# Chessbot_v7.net
KiCad netlist of a schematic drawn in EAGLE
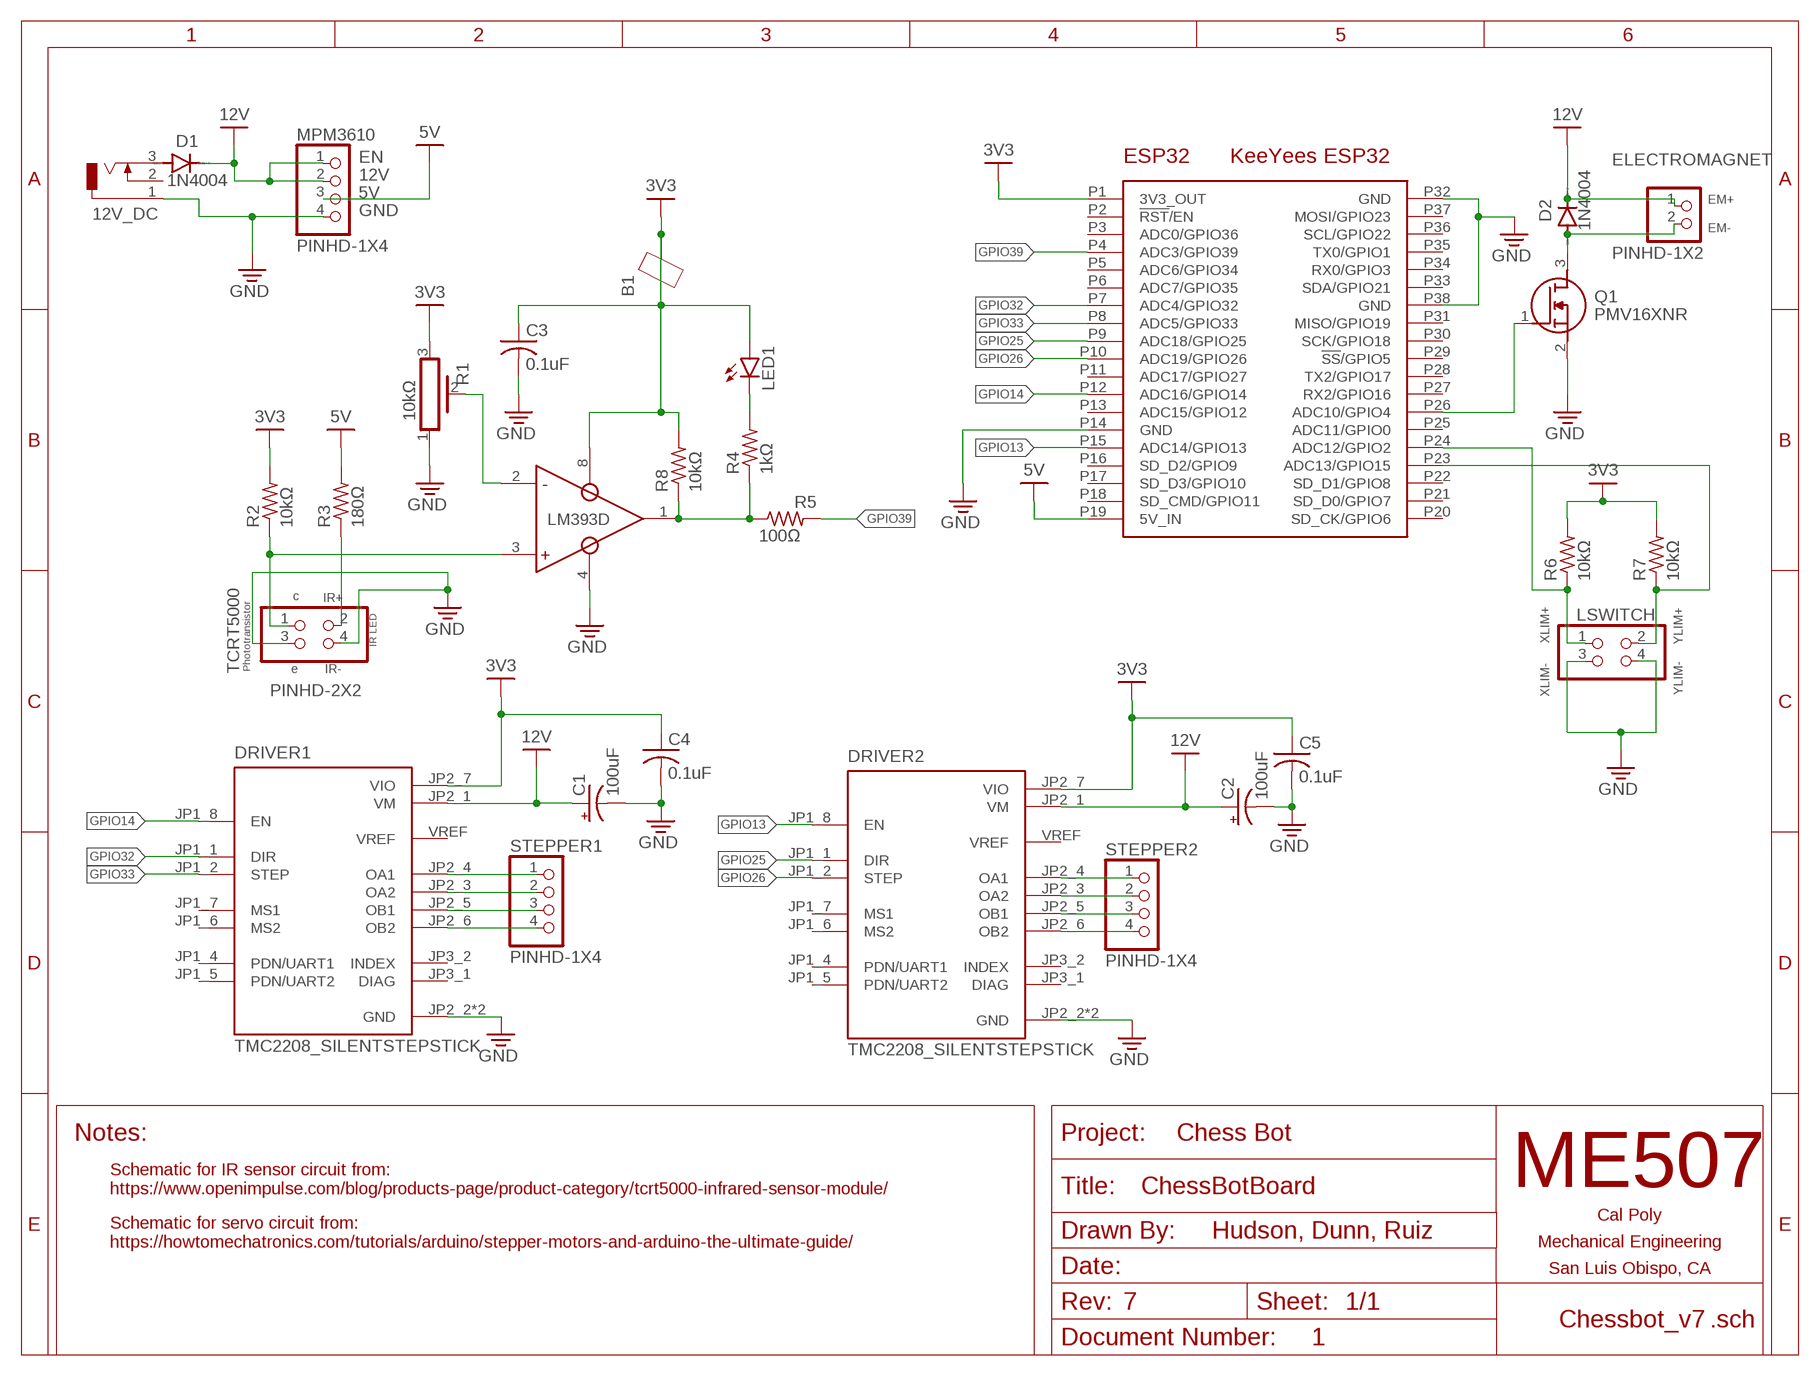
[diagram p0: schematic, sheet 1]

(export (version "E")
  (design (tool "Eeschema 10.0.6"))
  (components
    (comp (ref "12V_DC")
      (value "DCJ0303")
      (footprint "eagle-import:DCJ0303")
      (libsource (lib "eagle-import") (part "DCJ0303"))
    )
    (comp (ref "B1")
      (value "BEAD0805")
      (footprint "eagle-import:0805")
      (libsource (lib "eagle-import") (part "BEAD0805"))
    )
    (comp (ref "C1")
      (value "100uF")
      (footprint "eagle-import:E2,5-6")
      (libsource (lib "eagle-import") (part "CPOL-USE2.5-6"))
    )
    (comp (ref "C2")
      (value "100uF")
      (footprint "eagle-import:E2,5-6")
      (libsource (lib "eagle-import") (part "CPOL-USE2.5-6"))
    )
    (comp (ref "C3")
      (value "0.1uF")
      (footprint "eagle-import:C0805")
      (libsource (lib "eagle-import") (part "C-USC0805"))
    )
    (comp (ref "C4")
      (value "0.1uF")
      (footprint "eagle-import:C0805")
      (libsource (lib "eagle-import") (part "C-USC0805"))
    )
    (comp (ref "C5")
      (value "0.1uF")
      (footprint "eagle-import:C0805")
      (libsource (lib "eagle-import") (part "C-USC0805"))
    )
    (comp (ref "D1")
      (value "1N4004")
      (footprint "eagle-import:DO41-10")
      (libsource (lib "eagle-import") (part "1N4004"))
    )
    (comp (ref "D2")
      (value "1N4004")
      (footprint "eagle-import:DO41-10")
      (libsource (lib "eagle-import") (part "1N4004"))
    )
    (comp (ref "DRIVER1")
      (value "TMC2208_SILENTSTEPSTICK")
      (footprint "eagle-import:MODULE_TMC2208_SILENTSTEPSTICK")
      (fields (field (name "MF") "Trinamic Motion") (field (name "MP") "TMC2208 SILENTSTEPSTICK"))
      (libsource (lib "eagle-import") (part "TMC2208_SILENTSTEPSTICK"))
    )
    (comp (ref "DRIVER2")
      (value "TMC2208_SILENTSTEPSTICK")
      (footprint "eagle-import:MODULE_TMC2208_SILENTSTEPSTICK")
      (fields (field (name "MF") "Trinamic Motion") (field (name "MP") "TMC2208 SILENTSTEPSTICK"))
      (libsource (lib "eagle-import") (part "TMC2208_SILENTSTEPSTICK"))
    )
    (comp (ref "ELECTROMAGNET")
      (value "PINHD-1X2")
      (footprint "eagle-import:1X02")
      (libsource (lib "eagle-import") (part "PINHD-1X2"))
    )
    (comp (ref "ESP32")
      (value "KEEYEES_ESP32")
      (footprint "eagle-import:KEEYEES_ESP32")
      (libsource (lib "eagle-import") (part "KEEYEES_ESP32"))
    )
    (comp (ref "LED1")
      (value "LEDSMT1206")
      (footprint "eagle-import:1206")
      (libsource (lib "eagle-import") (part "LEDSMT1206"))
    )
    (comp (ref "LSWITCH")
      (value "PINHD-2X2")
      (footprint "eagle-import:2X02")
      (libsource (lib "eagle-import") (part "pinhead_325_PINHD-2X2"))
    )
    (comp (ref "MPM3610")
      (value "PINHD-1X4")
      (footprint "eagle-import:1X04")
      (libsource (lib "eagle-import") (part "PINHD-1X4"))
    )
    (comp (ref "Q1")
      (value "PMV16XNR")
      (footprint "eagle-import:SOT95P230X110-3N")
      (fields (field (name "MOUSER_PART_NUMBER") "771-PMV16XNR"))
      (libsource (lib "eagle-import") (part "PMV16XNR"))
    )
    (comp (ref "R1")
      (value "10kΩ")
      (footprint "eagle-import:PV36Z")
      (fields (field (name "MANUFACTURER") "BOURNS") (field (name "MPN") "PV36Z"))
      (libsource (lib "eagle-import") (part "PV36Z"))
    )
    (comp (ref "R2")
      (value "10kΩ")
      (footprint "eagle-import:R0805")
      (libsource (lib "eagle-import") (part "R-US_R0805"))
    )
    (comp (ref "R3")
      (value "180Ω")
      (footprint "eagle-import:R0805")
      (libsource (lib "eagle-import") (part "R-US_R0805"))
    )
    (comp (ref "R4")
      (value "1kΩ")
      (footprint "eagle-import:R0805")
      (libsource (lib "eagle-import") (part "R-US_R0805"))
    )
    (comp (ref "R5")
      (value "100Ω")
      (footprint "eagle-import:R0805")
      (libsource (lib "eagle-import") (part "R-US_R0805"))
    )
    (comp (ref "R6")
      (value "10kΩ")
      (footprint "eagle-import:R0805")
      (libsource (lib "eagle-import") (part "R-US_R0805"))
    )
    (comp (ref "R7")
      (value "10kΩ")
      (footprint "eagle-import:R0805")
      (libsource (lib "eagle-import") (part "R-US_R0805"))
    )
    (comp (ref "R8")
      (value "10kΩ")
      (footprint "eagle-import:R0805")
      (libsource (lib "eagle-import") (part "R-US_R0805"))
    )
    (comp (ref "STEPPER1")
      (value "PINHD-1X4")
      (footprint "eagle-import:1X04")
      (libsource (lib "eagle-import") (part "PINHD-1X4"))
    )
    (comp (ref "STEPPER2")
      (value "PINHD-1X4")
      (footprint "eagle-import:1X04")
      (libsource (lib "eagle-import") (part "PINHD-1X4"))
    )
    (comp (ref "TCRT5000")
      (value "PINHD-2X2")
      (footprint "eagle-import:2X02")
      (libsource (lib "eagle-import") (part "PINHD-2X2"))
    )
    (comp (ref "U$2")
      (value "LM393D")
      (footprint "eagle-import:LM393D")
      (libsource (lib "eagle-import") (part "LM393D"))
    )
  )
  (nets
    (net (code "1") (name "3V3") (class "Default")
      (node (ref "B1") (pin "1") (pinfunction "1_1") (pintype "bidirectional"))
      (node (ref "B1") (pin "2") (pinfunction "2_2") (pintype "bidirectional"))
      (node (ref "C3") (pin "1") (pinfunction "1_1") (pintype "passive"))
      (node (ref "C4") (pin "1") (pinfunction "1_1") (pintype "passive"))
      (node (ref "C5") (pin "1") (pinfunction "1_1") (pintype "passive"))
      (node (ref "DRIVER1") (pin "JP2_7") (pinfunction "VIO_JP2_7") (pintype "power_in"))
      (node (ref "DRIVER2") (pin "JP2_7") (pinfunction "VIO_JP2_7") (pintype "power_in"))
      (node (ref "ESP32") (pin "P1") (pinfunction "3V3_OUT_P1") (pintype "power_in"))
      (node (ref "LED1") (pin "A") (pinfunction "A_A") (pintype "passive"))
      (node (ref "R1") (pin "3") (pinfunction "P$3_3") (pintype "passive"))
      (node (ref "R2") (pin "2") (pinfunction "2_2") (pintype "passive"))
      (node (ref "R6") (pin "2") (pinfunction "2_2") (pintype "passive"))
      (node (ref "R7") (pin "2") (pinfunction "2_2") (pintype "passive"))
      (node (ref "R8") (pin "2") (pinfunction "2_2") (pintype "passive"))
      (node (ref "U$2") (pin "8") (pinfunction "VCC_8") (pintype "power_in"))
    )
    (net (code "2") (name "5V") (class "Default")
      (node (ref "ESP32") (pin "P19") (pinfunction "5V_IN_P19") (pintype "power_in"))
      (node (ref "MPM3610") (pin "3") (pinfunction "3_3") (pintype "passive"))
      (node (ref "R3") (pin "2") (pinfunction "2_2") (pintype "passive"))
    )
    (net (code "3") (name "12V") (class "Default")
      (node (ref "C1") (pin "+") (pinfunction "+_+") (pintype "passive"))
      (node (ref "C2") (pin "+") (pinfunction "+_+") (pintype "passive"))
      (node (ref "D1") (pin "C") (pinfunction "C_C") (pintype "passive"))
      (node (ref "D2") (pin "C") (pinfunction "C_C") (pintype "passive"))
      (node (ref "DRIVER1") (pin "JP2_1") (pinfunction "VM_JP2_1") (pintype "power_in"))
      (node (ref "DRIVER2") (pin "JP2_1") (pinfunction "VM_JP2_1") (pintype "power_in"))
      (node (ref "ELECTROMAGNET") (pin "1") (pinfunction "1_1") (pintype "passive"))
      (node (ref "MPM3610") (pin "1") (pinfunction "1_1") (pintype "passive"))
      (node (ref "MPM3610") (pin "2") (pinfunction "2_2") (pintype "passive"))
    )
    (net (code "4") (name "GND") (class "Default")
      (node (ref "12V_DC") (pin "1") (pinfunction "1_1") (pintype "passive"))
      (node (ref "C1") (pin "-") (pinfunction "-_-") (pintype "passive"))
      (node (ref "C2") (pin "-") (pinfunction "-_-") (pintype "passive"))
      (node (ref "C3") (pin "2") (pinfunction "2_2") (pintype "passive"))
      (node (ref "C4") (pin "2") (pinfunction "2_2") (pintype "passive"))
      (node (ref "C5") (pin "2") (pinfunction "2_2") (pintype "passive"))
      (node (ref "DRIVER1") (pin "JP2_2") (pinfunction "GND_JP2_2") (pintype "power_in"))
      (node (ref "DRIVER1") (pin "JP2_8") (pinfunction "GND_JP2_8") (pintype "power_in"))
      (node (ref "DRIVER2") (pin "JP2_2") (pinfunction "GND_JP2_2") (pintype "power_in"))
      (node (ref "DRIVER2") (pin "JP2_8") (pinfunction "GND_JP2_8") (pintype "power_in"))
      (node (ref "ESP32") (pin "P14") (pinfunction "GND_P14") (pintype "power_in"))
      (node (ref "ESP32") (pin "P32") (pinfunction "GND_P32") (pintype "power_in"))
      (node (ref "ESP32") (pin "P38") (pinfunction "GND_P38") (pintype "power_in"))
      (node (ref "LSWITCH") (pin "3") (pinfunction "3_3") (pintype "passive"))
      (node (ref "LSWITCH") (pin "4") (pinfunction "4_4") (pintype "passive"))
      (node (ref "MPM3610") (pin "4") (pinfunction "4_4") (pintype "passive"))
      (node (ref "Q1") (pin "2") (pinfunction "S_2") (pintype "bidirectional"))
      (node (ref "R1") (pin "1") (pinfunction "P$1_1") (pintype "passive"))
      (node (ref "TCRT5000") (pin "3") (pinfunction "3_3") (pintype "passive"))
      (node (ref "TCRT5000") (pin "4") (pinfunction "4_4") (pintype "passive"))
      (node (ref "U$2") (pin "4") (pinfunction "GND_4") (pintype "power_in"))
    )
    (net (code "5") (name "GPIO13") (class "Default")
      (node (ref "DRIVER2") (pin "JP1_8") (pinfunction "EN_JP1_8") (pintype "input"))
      (node (ref "ESP32") (pin "P15") (pinfunction "ADC14/GPIO13_P15") (pintype "bidirectional"))
    )
    (net (code "6") (name "GPIO14") (class "Default")
      (node (ref "DRIVER1") (pin "JP1_8") (pinfunction "EN_JP1_8") (pintype "input"))
      (node (ref "ESP32") (pin "P12") (pinfunction "ADC16/GPIO14_P12") (pintype "bidirectional"))
    )
    (net (code "7") (name "GPIO25") (class "Default")
      (node (ref "DRIVER2") (pin "JP1_1") (pinfunction "DIR_JP1_1") (pintype "input"))
      (node (ref "ESP32") (pin "P9") (pinfunction "ADC18/GPIO25_P9") (pintype "bidirectional"))
    )
    (net (code "8") (name "GPIO26") (class "Default")
      (node (ref "DRIVER2") (pin "JP1_2") (pinfunction "STEP_JP1_2") (pintype "input"))
      (node (ref "ESP32") (pin "P10") (pinfunction "ADC19/GPIO26_P10") (pintype "bidirectional"))
    )
    (net (code "9") (name "GPIO32") (class "Default")
      (node (ref "DRIVER1") (pin "JP1_1") (pinfunction "DIR_JP1_1") (pintype "input"))
      (node (ref "ESP32") (pin "P7") (pinfunction "ADC4/GPIO32_P7") (pintype "bidirectional"))
    )
    (net (code "10") (name "GPIO33") (class "Default")
      (node (ref "DRIVER1") (pin "JP1_2") (pinfunction "STEP_JP1_2") (pintype "input"))
      (node (ref "ESP32") (pin "P8") (pinfunction "ADC5/GPIO33_P8") (pintype "bidirectional"))
    )
    (net (code "11") (name "GPIO39") (class "Default")
      (node (ref "ESP32") (pin "P4") (pinfunction "ADC3/GPIO39_P4") (pintype "bidirectional"))
      (node (ref "R5") (pin "2") (pinfunction "2_2") (pintype "passive"))
    )
    (net (code "12") (name "Net-(12V_DC-Pad3)") (class "Default")
      (node (ref "12V_DC") (pin "3") (pinfunction "3_3") (pintype "passive"))
      (node (ref "D1") (pin "A") (pinfunction "A_A") (pintype "passive"))
    )
    (net (code "13") (name "Net-(DRIVER1-OA1)") (class "Default")
      (node (ref "DRIVER1") (pin "JP2_4") (pinfunction "OA1_JP2_4") (pintype "passive"))
      (node (ref "STEPPER1") (pin "1") (pinfunction "1_1") (pintype "passive"))
    )
    (net (code "14") (name "Net-(DRIVER1-OA2)") (class "Default")
      (node (ref "DRIVER1") (pin "JP2_3") (pinfunction "OA2_JP2_3") (pintype "passive"))
      (node (ref "STEPPER1") (pin "2") (pinfunction "2_2") (pintype "passive"))
    )
    (net (code "15") (name "Net-(DRIVER1-OB1)") (class "Default")
      (node (ref "DRIVER1") (pin "JP2_5") (pinfunction "OB1_JP2_5") (pintype "passive"))
      (node (ref "STEPPER1") (pin "3") (pinfunction "3_3") (pintype "passive"))
    )
    (net (code "16") (name "Net-(DRIVER1-OB2)") (class "Default")
      (node (ref "DRIVER1") (pin "JP2_6") (pinfunction "OB2_JP2_6") (pintype "passive"))
      (node (ref "STEPPER1") (pin "4") (pinfunction "4_4") (pintype "passive"))
    )
    (net (code "17") (name "Net-(DRIVER2-OA1)") (class "Default")
      (node (ref "DRIVER2") (pin "JP2_4") (pinfunction "OA1_JP2_4") (pintype "passive"))
      (node (ref "STEPPER2") (pin "1") (pinfunction "1_1") (pintype "passive"))
    )
    (net (code "18") (name "Net-(DRIVER2-OA2)") (class "Default")
      (node (ref "DRIVER2") (pin "JP2_3") (pinfunction "OA2_JP2_3") (pintype "passive"))
      (node (ref "STEPPER2") (pin "2") (pinfunction "2_2") (pintype "passive"))
    )
    (net (code "19") (name "Net-(DRIVER2-OB1)") (class "Default")
      (node (ref "DRIVER2") (pin "JP2_5") (pinfunction "OB1_JP2_5") (pintype "passive"))
      (node (ref "STEPPER2") (pin "3") (pinfunction "3_3") (pintype "passive"))
    )
    (net (code "20") (name "Net-(DRIVER2-OB2)") (class "Default")
      (node (ref "DRIVER2") (pin "JP2_6") (pinfunction "OB2_JP2_6") (pintype "passive"))
      (node (ref "STEPPER2") (pin "4") (pinfunction "4_4") (pintype "passive"))
    )
    (net (code "21") (name "Net-(ESP32-ADC10{slash}GPIO4)") (class "Default")
      (node (ref "ESP32") (pin "P26") (pinfunction "ADC10/GPIO4_P26") (pintype "bidirectional"))
      (node (ref "Q1") (pin "1") (pinfunction "G_1") (pintype "bidirectional"))
    )
    (net (code "22") (name "Net-(ESP32-ADC12{slash}GPIO2)") (class "Default")
      (node (ref "ESP32") (pin "P24") (pinfunction "ADC12/GPIO2_P24") (pintype "bidirectional"))
      (node (ref "LSWITCH") (pin "1") (pinfunction "1_1") (pintype "passive"))
      (node (ref "R6") (pin "1") (pinfunction "1_1") (pintype "passive"))
    )
    (net (code "23") (name "Net-(ESP32-ADC13{slash}GPIO15)") (class "Default")
      (node (ref "ESP32") (pin "P23") (pinfunction "ADC13/GPIO15_P23") (pintype "bidirectional"))
      (node (ref "LSWITCH") (pin "2") (pinfunction "2_2") (pintype "passive"))
      (node (ref "R7") (pin "1") (pinfunction "1_1") (pintype "passive"))
    )
    (net (code "24") (name "Net-(LED1-PadC)") (class "Default")
      (node (ref "LED1") (pin "C") (pinfunction "C_C") (pintype "passive"))
      (node (ref "R4") (pin "2") (pinfunction "2_2") (pintype "passive"))
    )
    (net (code "25") (name "Net-(Q1-D)") (class "Default")
      (node (ref "D2") (pin "A") (pinfunction "A_A") (pintype "passive"))
      (node (ref "ELECTROMAGNET") (pin "2") (pinfunction "2_2") (pintype "passive"))
      (node (ref "Q1") (pin "3") (pinfunction "D_3") (pintype "bidirectional"))
    )
    (net (code "26") (name "Net-(R1-P$2)") (class "Default")
      (node (ref "R1") (pin "2") (pinfunction "P$2_2") (pintype "passive"))
      (node (ref "U$2") (pin "2") (pinfunction "IN-_2") (pintype "input"))
    )
    (net (code "27") (name "Net-(R3-Pad1)") (class "Default")
      (node (ref "R3") (pin "1") (pinfunction "1_1") (pintype "passive"))
      (node (ref "TCRT5000") (pin "2") (pinfunction "2_2") (pintype "passive"))
    )
    (net (code "28") (name "Net-(U$2B-IN+)") (class "Default")
      (node (ref "R2") (pin "1") (pinfunction "1_1") (pintype "passive"))
      (node (ref "TCRT5000") (pin "1") (pinfunction "1_1") (pintype "passive"))
      (node (ref "U$2") (pin "3") (pinfunction "IN+_3") (pintype "input"))
    )
    (net (code "29") (name "Net-(U$2B-OUT)") (class "Default")
      (node (ref "R4") (pin "1") (pinfunction "1_1") (pintype "passive"))
      (node (ref "R5") (pin "1") (pinfunction "1_1") (pintype "passive"))
      (node (ref "R8") (pin "1") (pinfunction "1_1") (pintype "passive"))
      (node (ref "U$2") (pin "1") (pinfunction "OUT_1") (pintype "output"))
    )
    (net (code "30") (name "unconnected-(12V_DC-Pad2)") (class "Default")
      (node (ref "12V_DC") (pin "2") (pinfunction "2_2") (pintype "passive"))
    )
    (net (code "31") (name "unconnected-(DRIVER1-DIAG-PadJP3_1)") (class "Default")
      (node (ref "DRIVER1") (pin "JP3_1") (pinfunction "DIAG_JP3_1") (pintype "output"))
    )
    (net (code "32") (name "unconnected-(DRIVER1-INDEX-PadJP3_2)") (class "Default")
      (node (ref "DRIVER1") (pin "JP3_2") (pinfunction "INDEX_JP3_2") (pintype "output"))
    )
    (net (code "33") (name "unconnected-(DRIVER1-MS1-PadJP1_7)") (class "Default")
      (node (ref "DRIVER1") (pin "JP1_7") (pinfunction "MS1_JP1_7") (pintype "input"))
    )
    (net (code "34") (name "unconnected-(DRIVER1-MS2-PadJP1_6)") (class "Default")
      (node (ref "DRIVER1") (pin "JP1_6") (pinfunction "MS2_JP1_6") (pintype "input"))
    )
    (net (code "35") (name "unconnected-(DRIVER1-PDN{slash}UART1-PadJP1_4)") (class "Default")
      (node (ref "DRIVER1") (pin "JP1_4") (pinfunction "PDN/UART1_JP1_4") (pintype "bidirectional"))
    )
    (net (code "36") (name "unconnected-(DRIVER1-PDN{slash}UART2-PadJP1_5)") (class "Default")
      (node (ref "DRIVER1") (pin "JP1_5") (pinfunction "PDN/UART2_JP1_5") (pintype "bidirectional"))
    )
    (net (code "37") (name "unconnected-(DRIVER1-PadVREF)") (class "Default")
      (node (ref "DRIVER1") (pin "VREF") (pinfunction "VREF_VREF") (pintype "passive"))
    )
    (net (code "38") (name "unconnected-(DRIVER2-DIAG-PadJP3_1)") (class "Default")
      (node (ref "DRIVER2") (pin "JP3_1") (pinfunction "DIAG_JP3_1") (pintype "output"))
    )
    (net (code "39") (name "unconnected-(DRIVER2-INDEX-PadJP3_2)") (class "Default")
      (node (ref "DRIVER2") (pin "JP3_2") (pinfunction "INDEX_JP3_2") (pintype "output"))
    )
    (net (code "40") (name "unconnected-(DRIVER2-MS1-PadJP1_7)") (class "Default")
      (node (ref "DRIVER2") (pin "JP1_7") (pinfunction "MS1_JP1_7") (pintype "input"))
    )
    (net (code "41") (name "unconnected-(DRIVER2-MS2-PadJP1_6)") (class "Default")
      (node (ref "DRIVER2") (pin "JP1_6") (pinfunction "MS2_JP1_6") (pintype "input"))
    )
    (net (code "42") (name "unconnected-(DRIVER2-PDN{slash}UART1-PadJP1_4)") (class "Default")
      (node (ref "DRIVER2") (pin "JP1_4") (pinfunction "PDN/UART1_JP1_4") (pintype "bidirectional"))
    )
    (net (code "43") (name "unconnected-(DRIVER2-PDN{slash}UART2-PadJP1_5)") (class "Default")
      (node (ref "DRIVER2") (pin "JP1_5") (pinfunction "PDN/UART2_JP1_5") (pintype "bidirectional"))
    )
    (net (code "44") (name "unconnected-(DRIVER2-PadVREF)") (class "Default")
      (node (ref "DRIVER2") (pin "VREF") (pinfunction "VREF_VREF") (pintype "passive"))
    )
    (net (code "45") (name "unconnected-(ESP32-ADC0{slash}GPIO36-PadP3)") (class "Default")
      (node (ref "ESP32") (pin "P3") (pinfunction "ADC0/GPIO36_P3") (pintype "bidirectional"))
    )
    (net (code "46") (name "unconnected-(ESP32-ADC6{slash}GPIO34-PadP5)") (class "Default")
      (node (ref "ESP32") (pin "P5") (pinfunction "ADC6/GPIO34_P5") (pintype "bidirectional"))
    )
    (net (code "47") (name "unconnected-(ESP32-ADC7{slash}GPIO35-PadP6)") (class "Default")
      (node (ref "ESP32") (pin "P6") (pinfunction "ADC7/GPIO35_P6") (pintype "bidirectional"))
    )
    (net (code "48") (name "unconnected-(ESP32-ADC11{slash}GPIO0-PadP25)") (class "Default")
      (node (ref "ESP32") (pin "P25") (pinfunction "ADC11/GPIO0_P25") (pintype "bidirectional"))
    )
    (net (code "49") (name "unconnected-(ESP32-ADC15{slash}GPIO12-PadP13)") (class "Default")
      (node (ref "ESP32") (pin "P13") (pinfunction "ADC15/GPIO12_P13") (pintype "bidirectional"))
    )
    (net (code "50") (name "unconnected-(ESP32-ADC17{slash}GPIO27-PadP11)") (class "Default")
      (node (ref "ESP32") (pin "P11") (pinfunction "ADC17/GPIO27_P11") (pintype "bidirectional"))
    )
    (net (code "51") (name "unconnected-(ESP32-MISO{slash}GPIO19-PadP31)") (class "Default")
      (node (ref "ESP32") (pin "P31") (pinfunction "MISO/GPIO19_P31") (pintype "bidirectional"))
    )
    (net (code "52") (name "unconnected-(ESP32-MOSI{slash}GPIO23-PadP37)") (class "Default")
      (node (ref "ESP32") (pin "P37") (pinfunction "MOSI/GPIO23_P37") (pintype "bidirectional"))
    )
    (net (code "53") (name "unconnected-(ESP32-RX0{slash}GPIO3-PadP34)") (class "Default")
      (node (ref "ESP32") (pin "P34") (pinfunction "RX0/GPIO3_P34") (pintype "bidirectional"))
    )
    (net (code "54") (name "unconnected-(ESP32-RX2{slash}GPIO16-PadP27)") (class "Default")
      (node (ref "ESP32") (pin "P27") (pinfunction "RX2/GPIO16_P27") (pintype "bidirectional"))
    )
    (net (code "55") (name "unconnected-(ESP32-SCK{slash}GPIO18-PadP30)") (class "Default")
      (node (ref "ESP32") (pin "P30") (pinfunction "SCK/GPIO18_P30") (pintype "bidirectional"))
    )
    (net (code "56") (name "unconnected-(ESP32-SCL{slash}GPIO22-PadP36)") (class "Default")
      (node (ref "ESP32") (pin "P36") (pinfunction "SCL/GPIO22_P36") (pintype "bidirectional"))
    )
    (net (code "57") (name "unconnected-(ESP32-SDA{slash}GPIO21-PadP33)") (class "Default")
      (node (ref "ESP32") (pin "P33") (pinfunction "SDA/GPIO21_P33") (pintype "bidirectional"))
    )
    (net (code "58") (name "unconnected-(ESP32-SD_CK{slash}GPIO6-PadP20)") (class "Default")
      (node (ref "ESP32") (pin "P20") (pinfunction "SD_CK/GPIO6_P20") (pintype "bidirectional"))
    )
    (net (code "59") (name "unconnected-(ESP32-SD_CMD{slash}GPIO11-PadP18)") (class "Default")
      (node (ref "ESP32") (pin "P18") (pinfunction "SD_CMD/GPIO11_P18") (pintype "bidirectional"))
    )
    (net (code "60") (name "unconnected-(ESP32-SD_D0{slash}GPIO7-PadP21)") (class "Default")
      (node (ref "ESP32") (pin "P21") (pinfunction "SD_D0/GPIO7_P21") (pintype "bidirectional"))
    )
    (net (code "61") (name "unconnected-(ESP32-SD_D1{slash}GPIO8-PadP22)") (class "Default")
      (node (ref "ESP32") (pin "P22") (pinfunction "SD_D1/GPIO8_P22") (pintype "bidirectional"))
    )
    (net (code "62") (name "unconnected-(ESP32-SD_D2{slash}GPIO9-PadP16)") (class "Default")
      (node (ref "ESP32") (pin "P16") (pinfunction "SD_D2/GPIO9_P16") (pintype "bidirectional"))
    )
    (net (code "63") (name "unconnected-(ESP32-SD_D3{slash}GPIO10-PadP17)") (class "Default")
      (node (ref "ESP32") (pin "P17") (pinfunction "SD_D3/GPIO10_P17") (pintype "bidirectional"))
    )
    (net (code "64") (name "unconnected-(ESP32-TX0{slash}GPIO1-PadP35)") (class "Default")
      (node (ref "ESP32") (pin "P35") (pinfunction "TX0/GPIO1_P35") (pintype "bidirectional"))
    )
    (net (code "65") (name "unconnected-(ESP32-TX2{slash}GPIO17-PadP28)") (class "Default")
      (node (ref "ESP32") (pin "P28") (pinfunction "TX2/GPIO17_P28") (pintype "bidirectional"))
    )
    (net (code "66") (name "unconnected-(ESP32-~{RST}{slash}EN-PadP2)") (class "Default")
      (node (ref "ESP32") (pin "P2") (pinfunction "~{RST}/EN_P2") (pintype "input"))
    )
    (net (code "67") (name "unconnected-(ESP32-~{SS}{slash}GPIO5-PadP29)") (class "Default")
      (node (ref "ESP32") (pin "P29") (pinfunction "~{SS}/GPIO5_P29") (pintype "bidirectional"))
    )
  )
)
